# Test_PCB.net
KiCad netlist of a schematic drawn in Altium Designer
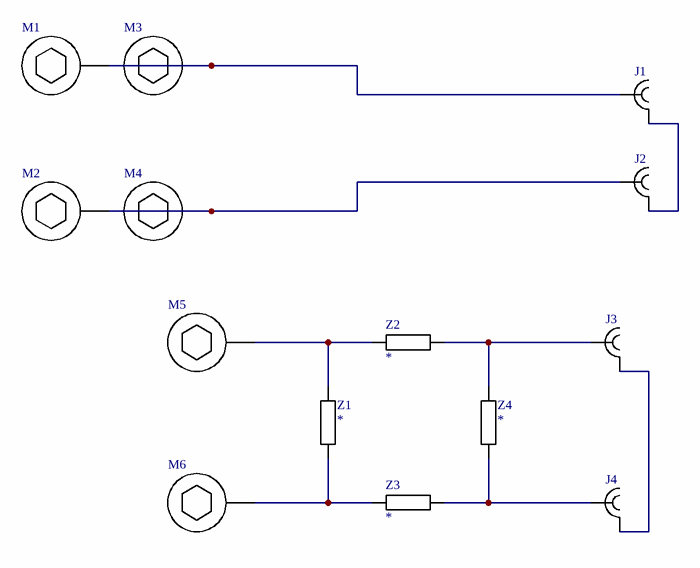
[diagram p0: Test_PCB.SchDoc]

(export (version "E")
  (design (tool "Eeschema 10.0.6"))
  (components
    (comp (ref "J1")
      (value "CONSMA001-G")
      (footprint "SMA TH Vertical Linx CONSMA001-G")
      (description "SMA TH VERTICAL LINX CONSMA001-G")
      (libsource (lib "Connector") (part "SMA TH VERTICAL LINX CONSMA001-G"))
    )
    (comp (ref "J2")
      (value "CONSMA001-G")
      (footprint "SMA TH Vertical Linx CONSMA001-G")
      (description "SMA TH VERTICAL LINX CONSMA001-G")
      (libsource (lib "Connector") (part "SMA TH VERTICAL LINX CONSMA001-G"))
    )
    (comp (ref "J3")
      (value "CONSMA001-G")
      (footprint "SMA TH Vertical Linx CONSMA001-G")
      (description "SMA TH VERTICAL LINX CONSMA001-G")
      (libsource (lib "Connector") (part "SMA TH VERTICAL LINX CONSMA001-G"))
    )
    (comp (ref "J4")
      (value "CONSMA001-G")
      (footprint "SMA TH Vertical Linx CONSMA001-G")
      (description "SMA TH VERTICAL LINX CONSMA001-G")
      (libsource (lib "Connector") (part "SMA TH VERTICAL LINX CONSMA001-G"))
    )
    (comp (ref "M1")
      (value "~")
      (footprint "Screw Hex Socket M2.5X4 Connected")
      (description "Screw Hex Socket Connected BN610")
      (libsource (lib "Mechanic") (part "Screw Hex Socket Connected"))
    )
    (comp (ref "M2")
      (value "~")
      (footprint "Screw Hex Socket M2.5X4 Connected")
      (description "Screw Hex Socket Connected BN610")
      (libsource (lib "Mechanic") (part "Screw Hex Socket Connected"))
    )
    (comp (ref "M3")
      (value "~")
      (footprint "Screw Hex Socket M2.5X4 Connected")
      (description "Screw Hex Socket Connected BN610")
      (libsource (lib "Mechanic") (part "Screw Hex Socket Connected"))
    )
    (comp (ref "M4")
      (value "~")
      (footprint "Screw Hex Socket M2.5X4 Connected")
      (description "Screw Hex Socket Connected BN610")
      (libsource (lib "Mechanic") (part "Screw Hex Socket Connected"))
    )
    (comp (ref "M5")
      (value "~")
      (footprint "Screw Hex Socket M2.5X4 Connected")
      (description "Screw Hex Socket Connected BN610")
      (libsource (lib "Mechanic") (part "Screw Hex Socket Connected"))
    )
    (comp (ref "M6")
      (value "~")
      (footprint "Screw Hex Socket M2.5X4 Connected")
      (description "Screw Hex Socket Connected BN610")
      (libsource (lib "Mechanic") (part "Screw Hex Socket Connected"))
    )
    (comp (ref "Z1")
      (value "*")
      (footprint "RESISTOR 2012 REFLOW")
      (description "Resistor")
      (libsource (lib "Resistor") (part "Resistor"))
    )
    (comp (ref "Z2")
      (value "*")
      (footprint "RESISTOR 2012 REFLOW")
      (description "Resistor")
      (libsource (lib "Resistor") (part "Resistor"))
    )
    (comp (ref "Z3")
      (value "*")
      (footprint "RESISTOR 2012 REFLOW")
      (description "Resistor")
      (libsource (lib "Resistor") (part "Resistor"))
    )
    (comp (ref "Z4")
      (value "*")
      (footprint "RESISTOR 2012 REFLOW")
      (description "Resistor")
      (libsource (lib "Resistor") (part "Resistor"))
    )
  )
  (nets
    (net (code "1") (name "Net-(J1-Pad1)") (class "Default")
      (node (ref "J1") (pin "1") (pinfunction "1_1") (pintype "passive"))
      (node (ref "M1") (pin "1") (pinfunction "1_1") (pintype "passive"))
      (node (ref "M3") (pin "1") (pinfunction "1_1") (pintype "passive"))
    )
    (net (code "2") (name "Net-(J1-Pad2)") (class "Default")
      (node (ref "J1") (pin "2") (pinfunction "2_2") (pintype "passive"))
      (node (ref "J2") (pin "2") (pinfunction "2_2") (pintype "passive"))
    )
    (net (code "3") (name "Net-(J2-Pad1)") (class "Default")
      (node (ref "J2") (pin "1") (pinfunction "1_1") (pintype "passive"))
      (node (ref "M2") (pin "1") (pinfunction "1_1") (pintype "passive"))
      (node (ref "M4") (pin "1") (pinfunction "1_1") (pintype "passive"))
    )
    (net (code "4") (name "Net-(J3-Pad1)") (class "Default")
      (node (ref "J3") (pin "1") (pinfunction "1_1") (pintype "passive"))
      (node (ref "Z2") (pin "2") (pinfunction "2_2") (pintype "passive"))
      (node (ref "Z4") (pin "2") (pinfunction "2_2") (pintype "passive"))
    )
    (net (code "5") (name "Net-(J3-Pad2)") (class "Default")
      (node (ref "J3") (pin "2") (pinfunction "2_2") (pintype "passive"))
      (node (ref "J4") (pin "2") (pinfunction "2_2") (pintype "passive"))
    )
    (net (code "6") (name "Net-(J4-Pad1)") (class "Default")
      (node (ref "J4") (pin "1") (pinfunction "1_1") (pintype "passive"))
      (node (ref "Z3") (pin "2") (pinfunction "2_2") (pintype "passive"))
      (node (ref "Z4") (pin "1") (pinfunction "1_1") (pintype "passive"))
    )
    (net (code "7") (name "Net-(M5-Pad1)") (class "Default")
      (node (ref "M5") (pin "1") (pinfunction "1_1") (pintype "passive"))
      (node (ref "Z1") (pin "2") (pinfunction "2_2") (pintype "passive"))
      (node (ref "Z2") (pin "1") (pinfunction "1_1") (pintype "passive"))
    )
    (net (code "8") (name "Net-(M6-Pad1)") (class "Default")
      (node (ref "M6") (pin "1") (pinfunction "1_1") (pintype "passive"))
      (node (ref "Z1") (pin "1") (pinfunction "1_1") (pintype "passive"))
      (node (ref "Z3") (pin "1") (pinfunction "1_1") (pintype "passive"))
    )
  )
)
